# FPGA.net
KiCad netlist of a schematic drawn in Altium Designer
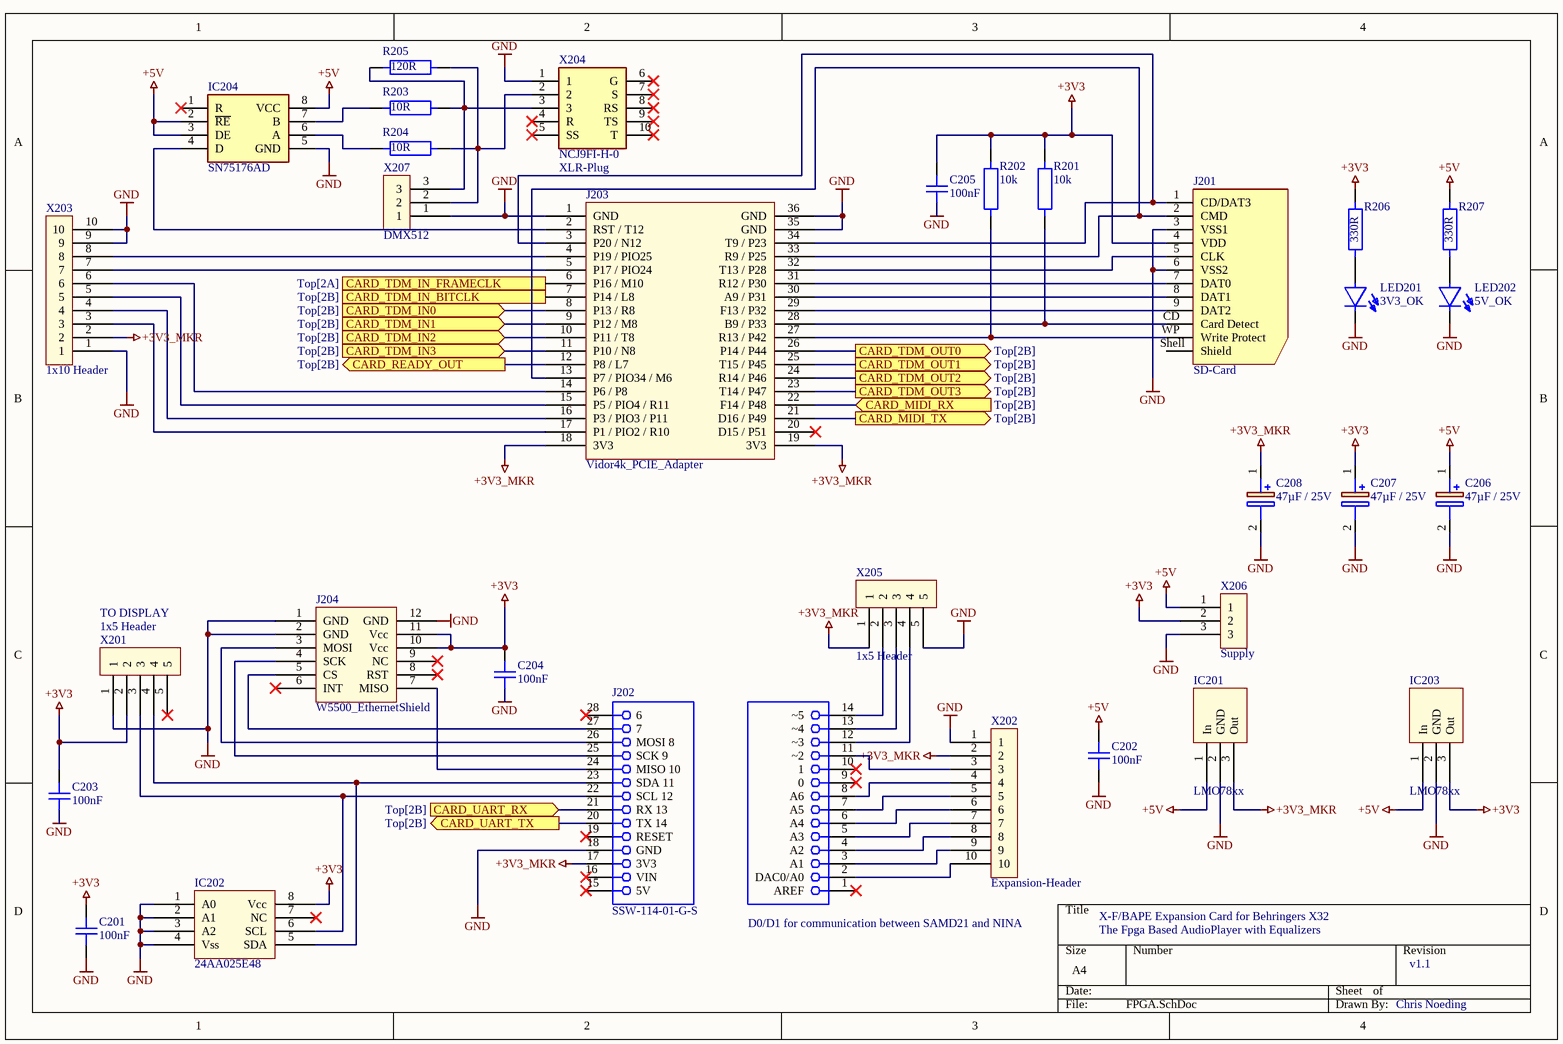
[diagram p0: FPGA.SchDoc]

(export (version "E")
  (design (tool "Eeschema 10.0.6"))
  (components
    (comp (ref "C201")
      (value "100nF")
      (footprint "1206")
      (description "1206_C")
      (libsource (lib "FPGA_Board_Library") (part "1206_C_1nF/63V"))
    )
    (comp (ref "C202")
      (value "100nF")
      (footprint "1206")
      (description "1206_C")
      (libsource (lib "FPGA_Board_Library") (part "1206_C_1nF/63V"))
    )
    (comp (ref "C203")
      (value "100nF")
      (footprint "1206")
      (description "1206_C")
      (libsource (lib "FPGA_Board_Library") (part "1206_C_1nF/63V"))
    )
    (comp (ref "C204")
      (value "100nF")
      (footprint "1206")
      (description "1206_C")
      (libsource (lib "FPGA_Board_Library") (part "1206_C_1nF/63V"))
    )
    (comp (ref "C205")
      (value "100nF")
      (footprint "1206")
      (description "1206_C")
      (libsource (lib "FPGA_Board_Library") (part "1206_C_1nF/63V"))
    )
    (comp (ref "C206")
      (value "47µF / 25V")
      (footprint "SamacSys:CAPPRD200W50D550H1250")
      (description "Capacitor Polarised")
      (fields (field (name "MANUFACTURER_PART_NUMBER") "MAL214256479E3"))
      (libsource (lib "*") (part "MAL214256479E3"))
    )
    (comp (ref "C207")
      (value "47µF / 25V")
      (footprint "SamacSys:CAPPRD200W50D550H1250")
      (description "Capacitor Polarised")
      (fields (field (name "MANUFACTURER_PART_NUMBER") "MAL214256479E3"))
      (libsource (lib "*") (part "MAL214256479E3"))
    )
    (comp (ref "C208")
      (value "47µF / 25V")
      (footprint "SamacSys:CAPPRD200W50D550H1250")
      (description "Capacitor Polarised")
      (fields (field (name "MANUFACTURER_PART_NUMBER") "MAL214256479E3"))
      (libsource (lib "*") (part "MAL214256479E3"))
    )
    (comp (ref "IC201")
      (value "LMO78xx")
      (footprint "LMO78xx")
      (libsource (lib "KDEE_HiResPG") (part "LMO78xx"))
    )
    (comp (ref "IC202")
      (value "24AA025E48")
      (footprint "SOIC-8")
      (libsource (lib "KDEE_HiResPG") (part "24AA025E48"))
    )
    (comp (ref "IC203")
      (value "LMO78xx")
      (footprint "LMO78xx")
      (libsource (lib "KDEE_HiResPG") (part "LMO78xx"))
    )
    (comp (ref "IC204")
      (value "SN75176AD")
      (footprint "SamacSys:SOIC127P600X175-8N")
      (description "Integrated Circuit")
      (fields (field (name "MOUSER PART NUMBER") "595-SN75176AD"))
      (libsource (lib "*") (part "SN75176AD"))
    )
    (comp (ref "J201")
      (value "693061010911")
      (footprint "693061010911")
      (description "WR-CRD SD Card Connector Push & Push with Card Detection")
      (fields (field (name "MANUFACTURER") "Wurth Elektronik"))
      (libsource (lib "SamacSys") (part "693061010911"))
    )
    (comp (ref "J202")
      (value "SSW-114-01-G-S")
      (footprint "SMTC-SSW-114-01-X-S")
      (description "SQ Post Socket, Through-hole, Vertical, -55 to 125 degC, 2.54 mm Pitch, 14-Pin, Female, RoHS")
      (fields (field (name "MANUFACTURER") "Samtec"))
      (libsource (lib "SamacSys") (part "Arduino MKR Vidor 4000"))
    )
    (comp (ref "J203")
      (value "Vidor4k_PCIE_Adapter")
      (footprint "Vidor4K_PCIE_Adapter")
      (libsource (lib "SamacSys") (part "Vidor4k_PCIE_Adapter"))
    )
    (comp (ref "J204")
      (value "W5500_EthernetShield")
      (footprint "W5500_EthernetShield")
      (libsource (lib "KDEE_HiResPG") (part "W5500_EthernetShield"))
    )
    (comp (ref "LED201")
      (value "3V3_OK")
      (footprint "LED 3MM")
      (description "LED 3MM")
      (libsource (lib "FPGA_Board_Library") (part "LED 3MM"))
    )
    (comp (ref "LED202")
      (value "5V_OK")
      (footprint "LED 3MM")
      (description "LED 3MM")
      (libsource (lib "FPGA_Board_Library") (part "LED 3MM"))
    )
    (comp (ref "R201")
      (value "10k")
      (footprint "1206")
      (description "1206_R")
      (libsource (lib "FPGA_Board_Library") (part "1206_R"))
    )
    (comp (ref "R202")
      (value "10k")
      (footprint "1206")
      (description "1206_R")
      (libsource (lib "FPGA_Board_Library") (part "1206_R"))
    )
    (comp (ref "R203")
      (value "10R")
      (footprint "1206")
      (description "1206_R")
      (libsource (lib "FPGA_Board_Library") (part "1206_R"))
    )
    (comp (ref "R204")
      (value "10R")
      (footprint "1206")
      (description "1206_R")
      (libsource (lib "FPGA_Board_Library") (part "1206_R"))
    )
    (comp (ref "R205")
      (value "120R")
      (footprint "1206")
      (description "1206_R")
      (libsource (lib "FPGA_Board_Library") (part "1206_R"))
    )
    (comp (ref "R206")
      (value "330R")
      (footprint "1206")
      (description "1206_R")
      (libsource (lib "FPGA_Board_Library") (part "1206_R"))
    )
    (comp (ref "R207")
      (value "330R")
      (footprint "1206")
      (description "1206_R")
      (libsource (lib "FPGA_Board_Library") (part "1206_R"))
    )
    (comp (ref "X201")
      (value "1x5 Header")
      (footprint "1x5 Header")
      (libsource (lib "KDEE_HiResPG") (part "1x5 Header"))
    )
    (comp (ref "X202")
      (value "Expansion-Header")
      (footprint "1x10 Header")
      (libsource (lib "KDEE_HiResPG") (part "1x10 Header"))
    )
    (comp (ref "X203")
      (value "1x10 Header")
      (footprint "1x10 Header")
      (libsource (lib "") (part "1x10 Header_1"))
    )
    (comp (ref "X204")
      (value "NCJ9FI-H-0")
      (footprint "SamacSys:NCJ9FIH0")
      (description "Connector")
      (fields (field (name "MOUSER PART NUMBER") "568-NCJ9FI-H-O"))
      (libsource (lib "SamacSys") (part "NCJ9FI-H-0"))
    )
    (comp (ref "X205")
      (value "1x5 Header")
      (footprint "1x5 Header")
      (libsource (lib "KDEE_HiResPG") (part "1x5 Header"))
    )
    (comp (ref "X206")
      (value "Supply")
      (footprint "1x3 Jumper")
      (libsource (lib "KDEE_HiResPG") (part "1x3 Jumper"))
    )
    (comp (ref "X207") (value "DMX512") (footprint "1x3 Jumper") (libsource (lib "") (part "1x3 Jumper_1")))
  )
  (nets
    (net (code "1") (name "+3V3") (class "Default")
      (node (ref "C201") (pin "1") (pinfunction "1_1") (pintype "passive"))
      (node (ref "C203") (pin "1") (pinfunction "1_1") (pintype "passive"))
      (node (ref "C204") (pin "1") (pinfunction "1_1") (pintype "passive"))
      (node (ref "C205") (pin "1") (pinfunction "1_1") (pintype "passive"))
      (node (ref "C207") (pin "1") (pinfunction "+_1") (pintype "passive"))
      (node (ref "IC202") (pin "8") (pinfunction "Vcc_8") (pintype "passive"))
      (node (ref "IC203") (pin "3") (pinfunction "Out_3") (pintype "passive"))
      (node (ref "J201") (pin "4") (pinfunction "VDD_4") (pintype "passive"))
      (node (ref "J204") (pin "10") (pinfunction "Vcc_10") (pintype "passive"))
      (node (ref "J204") (pin "11") (pinfunction "Vcc_11") (pintype "passive"))
      (node (ref "R201") (pin "2") (pinfunction "2_2") (pintype "passive"))
      (node (ref "R202") (pin "2") (pinfunction "2_2") (pintype "passive"))
      (node (ref "R206") (pin "1") (pinfunction "1_1") (pintype "passive"))
      (node (ref "X201") (pin "2") (pinfunction "2_2") (pintype "passive"))
      (node (ref "X206") (pin "2") (pinfunction "2_2") (pintype "passive"))
    )
    (net (code "2") (name "+3V3_MKR") (class "Default")
      (node (ref "C208") (pin "1") (pinfunction "+_1") (pintype "passive"))
      (node (ref "IC201") (pin "3") (pinfunction "Out_3") (pintype "passive"))
      (node (ref "J202") (pin "17") (pinfunction "3V3_17") (pintype "passive"))
      (node (ref "J203") (pin "18") (pinfunction "3V3_18") (pintype "passive"))
      (node (ref "J203") (pin "19") (pinfunction "3V3_19") (pintype "passive"))
      (node (ref "X202") (pin "2") (pinfunction "2_2") (pintype "passive"))
      (node (ref "X203") (pin "2") (pinfunction "2_2") (pintype "passive"))
      (node (ref "X205") (pin "1") (pinfunction "1_1") (pintype "passive"))
    )
    (net (code "3") (name "+5V") (class "Default")
      (node (ref "C202") (pin "1") (pinfunction "1_1") (pintype "passive"))
      (node (ref "C206") (pin "1") (pinfunction "+_1") (pintype "passive"))
      (node (ref "IC201") (pin "1") (pinfunction "In_1") (pintype "passive"))
      (node (ref "IC203") (pin "1") (pinfunction "In_1") (pintype "passive"))
      (node (ref "IC204") (pin "2") (pinfunction "~{RE}_2") (pintype "passive"))
      (node (ref "IC204") (pin "3") (pinfunction "DE_3") (pintype "passive"))
      (node (ref "IC204") (pin "8") (pinfunction "VCC_8") (pintype "passive"))
      (node (ref "R207") (pin "1") (pinfunction "1_1") (pintype "passive"))
      (node (ref "X206") (pin "1") (pinfunction "1_1") (pintype "passive"))
    )
    (net (code "4") (name "/CARD_MIDI_RX") (class "Default")
      (node (ref "J203") (pin "22") (pinfunction "F14_/_P48_22") (pintype "passive"))
    )
    (net (code "5") (name "/CARD_MIDI_TX") (class "Default")
      (node (ref "J203") (pin "21") (pinfunction "D16_/_P49_21") (pintype "passive"))
    )
    (net (code "6") (name "/CARD_READY_OUT") (class "Default")
      (node (ref "J203") (pin "12") (pinfunction "P8_/_L7_12") (pintype "passive"))
    )
    (net (code "7") (name "/CARD_TDM_IN0") (class "Default")
      (node (ref "J203") (pin "8") (pinfunction "P13_/_R8_8") (pintype "passive"))
    )
    (net (code "8") (name "/CARD_TDM_IN1") (class "Default")
      (node (ref "J203") (pin "9") (pinfunction "P12_/_M8_9") (pintype "passive"))
    )
    (net (code "9") (name "/CARD_TDM_IN2") (class "Default")
      (node (ref "J203") (pin "10") (pinfunction "P11_/_T8_10") (pintype "passive"))
    )
    (net (code "10") (name "/CARD_TDM_IN3") (class "Default")
      (node (ref "J203") (pin "11") (pinfunction "P10_/_N8_11") (pintype "passive"))
    )
    (net (code "11") (name "/CARD_TDM_IN_BITCLK") (class "Default")
      (node (ref "J203") (pin "7") (pinfunction "P14_/_L8_7") (pintype "passive"))
    )
    (net (code "12") (name "/CARD_TDM_IN_FRAMECLK") (class "Default")
      (node (ref "J203") (pin "6") (pinfunction "P16_/_M10_6") (pintype "passive"))
    )
    (net (code "13") (name "/CARD_TDM_OUT0") (class "Default")
      (node (ref "J203") (pin "26") (pinfunction "P14_/_P44_26") (pintype "passive"))
    )
    (net (code "14") (name "/CARD_TDM_OUT1") (class "Default")
      (node (ref "J203") (pin "25") (pinfunction "T15_/_P45_25") (pintype "passive"))
    )
    (net (code "15") (name "/CARD_TDM_OUT2") (class "Default")
      (node (ref "J203") (pin "24") (pinfunction "R14_/_P46_24") (pintype "passive"))
    )
    (net (code "16") (name "/CARD_TDM_OUT3") (class "Default")
      (node (ref "J203") (pin "23") (pinfunction "T14_/_P47_23") (pintype "passive"))
    )
    (net (code "17") (name "/CARD_UART_RX") (class "Default")
      (node (ref "J202") (pin "21") (pinfunction "RX_13_21") (pintype "passive"))
    )
    (net (code "18") (name "/CARD_UART_TX") (class "Default")
      (node (ref "J202") (pin "20") (pinfunction "TX_14_20") (pintype "passive"))
    )
    (net (code "19") (name "GND") (class "Default")
      (node (ref "C201") (pin "2") (pinfunction "2_2") (pintype "passive"))
      (node (ref "C202") (pin "2") (pinfunction "2_2") (pintype "passive"))
      (node (ref "C203") (pin "2") (pinfunction "2_2") (pintype "passive"))
      (node (ref "C204") (pin "2") (pinfunction "2_2") (pintype "passive"))
      (node (ref "C205") (pin "2") (pinfunction "2_2") (pintype "passive"))
      (node (ref "C206") (pin "2") (pinfunction "-_2") (pintype "passive"))
      (node (ref "C207") (pin "2") (pinfunction "-_2") (pintype "passive"))
      (node (ref "C208") (pin "2") (pinfunction "-_2") (pintype "passive"))
      (node (ref "IC201") (pin "2") (pinfunction "GND_2") (pintype "passive"))
      (node (ref "IC202") (pin "1") (pinfunction "A0_1") (pintype "passive"))
      (node (ref "IC202") (pin "2") (pinfunction "A1_2") (pintype "passive"))
      (node (ref "IC202") (pin "3") (pinfunction "A2_3") (pintype "passive"))
      (node (ref "IC202") (pin "4") (pinfunction "Vss_4") (pintype "passive"))
      (node (ref "IC203") (pin "2") (pinfunction "GND_2") (pintype "passive"))
      (node (ref "IC204") (pin "5") (pinfunction "GND_5") (pintype "passive"))
      (node (ref "J201") (pin "3") (pinfunction "VSS1_3") (pintype "passive"))
      (node (ref "J201") (pin "6") (pinfunction "VSS2_6") (pintype "passive"))
      (node (ref "J202") (pin "18") (pinfunction "GND_18") (pintype "passive"))
      (node (ref "J203") (pin "1") (pinfunction "GND_1") (pintype "passive"))
      (node (ref "J203") (pin "35") (pinfunction "GND_35") (pintype "passive"))
      (node (ref "J203") (pin "36") (pinfunction "GND_36") (pintype "passive"))
      (node (ref "J204") (pin "1") (pinfunction "GND_1") (pintype "passive"))
      (node (ref "J204") (pin "12") (pinfunction "GND_12") (pintype "passive"))
      (node (ref "J204") (pin "2") (pinfunction "GND_2") (pintype "passive"))
      (node (ref "LED201") (pin "2") (pintype "passive"))
      (node (ref "LED202") (pin "2") (pintype "passive"))
      (node (ref "X201") (pin "1") (pinfunction "1_1") (pintype "passive"))
      (node (ref "X202") (pin "1") (pinfunction "1_1") (pintype "passive"))
      (node (ref "X203") (pin "1") (pinfunction "1_1") (pintype "passive"))
      (node (ref "X203") (pin "10") (pinfunction "10_10") (pintype "passive"))
      (node (ref "X203") (pin "9") (pinfunction "9_9") (pintype "passive"))
      (node (ref "X204") (pin "1") (pinfunction "1_1") (pintype "passive"))
      (node (ref "X205") (pin "5") (pinfunction "5_5") (pintype "passive"))
      (node (ref "X206") (pin "3") (pinfunction "3_3") (pintype "passive"))
      (node (ref "X207") (pin "1") (pinfunction "1_1") (pintype "passive"))
    )
    (net (code "20") (name "Net-(IC202-SCL)") (class "Default")
      (node (ref "IC202") (pin "6") (pinfunction "SCL_6") (pintype "passive"))
      (node (ref "J202") (pin "22") (pinfunction "SCL_12_22") (pintype "passive"))
      (node (ref "X201") (pin "3") (pinfunction "3_3") (pintype "passive"))
    )
    (net (code "21") (name "Net-(IC202-SDA)") (class "Default")
      (node (ref "IC202") (pin "5") (pinfunction "SDA_5") (pintype "passive"))
      (node (ref "J202") (pin "23") (pinfunction "SDA_11_23") (pintype "passive"))
      (node (ref "X201") (pin "4") (pinfunction "4_4") (pintype "passive"))
    )
    (net (code "22") (name "Net-(IC204-A)") (class "Default")
      (node (ref "IC204") (pin "6") (pinfunction "A_6") (pintype "passive"))
      (node (ref "R204") (pin "1") (pinfunction "1_1") (pintype "passive"))
    )
    (net (code "23") (name "Net-(IC204-B)") (class "Default")
      (node (ref "IC204") (pin "7") (pinfunction "B_7") (pintype "passive"))
      (node (ref "R203") (pin "1") (pinfunction "1_1") (pintype "passive"))
    )
    (net (code "24") (name "Net-(IC204-D)") (class "Default")
      (node (ref "IC204") (pin "4") (pinfunction "D_4") (pintype "passive"))
      (node (ref "J203") (pin "2") (pinfunction "RST_/_T12_2") (pintype "passive"))
    )
    (net (code "25") (name "Net-(J201-CD{slash}DAT3)") (class "Default")
      (node (ref "J201") (pin "1") (pinfunction "CD/DAT3_1") (pintype "passive"))
      (node (ref "J203") (pin "3") (pinfunction "P20_/_N12_3") (pintype "passive"))
      (node (ref "J203") (pin "34") (pinfunction "T9_/_P23_34") (pintype "passive"))
    )
    (net (code "26") (name "Net-(J201-CLK)") (class "Default")
      (node (ref "J201") (pin "5") (pinfunction "CLK_5") (pintype "passive"))
      (node (ref "J203") (pin "32") (pinfunction "T13_/_P28_32") (pintype "passive"))
    )
    (net (code "27") (name "Net-(J201-CMD)") (class "Default")
      (node (ref "J201") (pin "2") (pinfunction "CMD_2") (pintype "passive"))
      (node (ref "J203") (pin "13") (pinfunction "P7_/_PIO34_/_M6_13") (pintype "passive"))
      (node (ref "J203") (pin "33") (pinfunction "R9_/_P25_33") (pintype "passive"))
    )
    (net (code "28") (name "Net-(J201-Card_Detect)") (class "Default")
      (node (ref "J201") (pin "CD") (pinfunction "Card_Detect_CD") (pintype "passive"))
      (node (ref "J203") (pin "28") (pinfunction "B9_/_P33_28") (pintype "passive"))
      (node (ref "R201") (pin "1") (pinfunction "1_1") (pintype "passive"))
    )
    (net (code "29") (name "Net-(J201-DAT0)") (class "Default")
      (node (ref "J201") (pin "7") (pinfunction "DAT0_7") (pintype "passive"))
      (node (ref "J203") (pin "31") (pinfunction "R12_/_P30_31") (pintype "passive"))
    )
    (net (code "30") (name "Net-(J201-DAT1)") (class "Default")
      (node (ref "J201") (pin "8") (pinfunction "DAT1_8") (pintype "passive"))
      (node (ref "J203") (pin "30") (pinfunction "A9_/_P31_30") (pintype "passive"))
    )
    (net (code "31") (name "Net-(J201-DAT2)") (class "Default")
      (node (ref "J201") (pin "9") (pinfunction "DAT2_9") (pintype "passive"))
      (node (ref "J203") (pin "29") (pinfunction "F13_/_P32_29") (pintype "passive"))
    )
    (net (code "32") (name "Net-(J201-Write_Protect)") (class "Default")
      (node (ref "J201") (pin "WP") (pinfunction "Write_Protect_WP") (pintype "passive"))
      (node (ref "J203") (pin "27") (pinfunction "R13_/_P42_27") (pintype "passive"))
      (node (ref "R202") (pin "1") (pinfunction "1_1") (pintype "passive"))
    )
    (net (code "33") (name "Net-(J202-7)") (class "Default")
      (node (ref "J202") (pin "27") (pinfunction "7_27") (pintype "passive"))
      (node (ref "J204") (pin "5") (pinfunction "CS_5") (pintype "passive"))
    )
    (net (code "34") (name "Net-(J202-A1)") (class "Default")
      (node (ref "J202") (pin "3") (pinfunction "A1_3") (pintype "passive"))
      (node (ref "X202") (pin "9") (pinfunction "9_9") (pintype "passive"))
    )
    (net (code "35") (name "Net-(J202-A2)") (class "Default")
      (node (ref "J202") (pin "4") (pinfunction "A2_4") (pintype "passive"))
      (node (ref "X202") (pin "8") (pinfunction "8_8") (pintype "passive"))
    )
    (net (code "36") (name "Net-(J202-A3)") (class "Default")
      (node (ref "J202") (pin "5") (pinfunction "A3_5") (pintype "passive"))
      (node (ref "X202") (pin "7") (pinfunction "7_7") (pintype "passive"))
    )
    (net (code "37") (name "Net-(J202-A4)") (class "Default")
      (node (ref "J202") (pin "6") (pinfunction "A4_6") (pintype "passive"))
      (node (ref "X202") (pin "6") (pinfunction "6_6") (pintype "passive"))
    )
    (net (code "38") (name "Net-(J202-A5)") (class "Default")
      (node (ref "J202") (pin "7") (pinfunction "A5_7") (pintype "passive"))
      (node (ref "X202") (pin "5") (pinfunction "5_5") (pintype "passive"))
    )
    (net (code "39") (name "Net-(J202-A6)") (class "Default")
      (node (ref "J202") (pin "8") (pinfunction "A6_8") (pintype "passive"))
      (node (ref "X202") (pin "4") (pinfunction "4_4") (pintype "passive"))
    )
    (net (code "40") (name "Net-(J202-DAC0{slash}A0)") (class "Default")
      (node (ref "J202") (pin "2") (pinfunction "DAC0/A0_2") (pintype "passive"))
      (node (ref "X202") (pin "10") (pinfunction "10_10") (pintype "passive"))
    )
    (net (code "41") (name "Net-(J202-MISO_10)") (class "Default")
      (node (ref "J202") (pin "24") (pinfunction "MISO_10_24") (pintype "passive"))
      (node (ref "J204") (pin "7") (pinfunction "MISO_7") (pintype "passive"))
    )
    (net (code "42") (name "Net-(J202-MOSI_8)") (class "Default")
      (node (ref "J202") (pin "26") (pinfunction "MOSI_8_26") (pintype "passive"))
      (node (ref "J204") (pin "3") (pinfunction "MOSI_3") (pintype "passive"))
    )
    (net (code "43") (name "Net-(J202-SCK_9)") (class "Default")
      (node (ref "J202") (pin "25") (pinfunction "SCK_9_25") (pintype "passive"))
      (node (ref "J204") (pin "4") (pinfunction "SCK_4") (pintype "passive"))
    )
    (net (code "44") (name "Net-(J202-~2)") (class "Default")
      (node (ref "J202") (pin "11") (pinfunction "~2_11") (pintype "passive"))
      (node (ref "X202") (pin "3") (pinfunction "3_3") (pintype "passive"))
    )
    (net (code "45") (name "Net-(J202-~3)") (class "Default")
      (node (ref "J202") (pin "12") (pinfunction "~3_12") (pintype "passive"))
      (node (ref "X205") (pin "4") (pinfunction "4_4") (pintype "passive"))
    )
    (net (code "46") (name "Net-(J202-~4)") (class "Default")
      (node (ref "J202") (pin "13") (pinfunction "~4_13") (pintype "passive"))
      (node (ref "X205") (pin "3") (pinfunction "3_3") (pintype "passive"))
    )
    (net (code "47") (name "Net-(J202-~5)") (class "Default")
      (node (ref "J202") (pin "14") (pinfunction "~5_14") (pintype "passive"))
      (node (ref "X205") (pin "2") (pinfunction "2_2") (pintype "passive"))
    )
    (net (code "48") (name "Net-(J203-P1_{slash}_PIO2_{slash}_R10)") (class "Default")
      (node (ref "J203") (pin "17") (pinfunction "P1_/_PIO2_/_R10_17") (pintype "passive"))
      (node (ref "X203") (pin "3") (pinfunction "3_3") (pintype "passive"))
    )
    (net (code "49") (name "Net-(J203-P3_{slash}_PIO3_{slash}_P11)") (class "Default")
      (node (ref "J203") (pin "16") (pinfunction "P3_/_PIO3_/_P11_16") (pintype "passive"))
      (node (ref "X203") (pin "4") (pinfunction "4_4") (pintype "passive"))
    )
    (net (code "50") (name "Net-(J203-P5_{slash}_PIO4_{slash}_R11)") (class "Default")
      (node (ref "J203") (pin "15") (pinfunction "P5_/_PIO4_/_R11_15") (pintype "passive"))
      (node (ref "X203") (pin "5") (pinfunction "5_5") (pintype "passive"))
    )
    (net (code "51") (name "Net-(J203-P6_{slash}_P8)") (class "Default")
      (node (ref "J203") (pin "14") (pinfunction "P6_/_P8_14") (pintype "passive"))
      (node (ref "X203") (pin "6") (pinfunction "6_6") (pintype "passive"))
    )
    (net (code "52") (name "Net-(J203-P17_{slash}_PIO24)") (class "Default")
      (node (ref "J203") (pin "5") (pinfunction "P17_/_PIO24_5") (pintype "passive"))
      (node (ref "X203") (pin "7") (pinfunction "7_7") (pintype "passive"))
    )
    (net (code "53") (name "Net-(J203-P19_{slash}_PIO25)") (class "Default")
      (node (ref "J203") (pin "4") (pinfunction "P19_/_PIO25_4") (pintype "passive"))
      (node (ref "X203") (pin "8") (pinfunction "8_8") (pintype "passive"))
    )
    (net (code "54") (name "Net-(LED201-Pad1)") (class "Default")
      (node (ref "LED201") (pin "1") (pintype "passive"))
      (node (ref "R206") (pin "2") (pinfunction "2_2") (pintype "passive"))
    )
    (net (code "55") (name "Net-(LED202-Pad1)") (class "Default")
      (node (ref "LED202") (pin "1") (pintype "passive"))
      (node (ref "R207") (pin "2") (pinfunction "2_2") (pintype "passive"))
    )
    (net (code "56") (name "Net-(R203-Pad2)") (class "Default")
      (node (ref "R203") (pin "2") (pinfunction "2_2") (pintype "passive"))
      (node (ref "R205") (pin "1") (pinfunction "1_1") (pintype "passive"))
      (node (ref "X204") (pin "3") (pinfunction "3_3") (pintype "passive"))
      (node (ref "X207") (pin "3") (pinfunction "3_3") (pintype "passive"))
    )
    (net (code "57") (name "Net-(R204-Pad2)") (class "Default")
      (node (ref "R204") (pin "2") (pinfunction "2_2") (pintype "passive"))
      (node (ref "R205") (pin "2") (pinfunction "2_2") (pintype "passive"))
      (node (ref "X204") (pin "2") (pinfunction "2_2") (pintype "passive"))
      (node (ref "X207") (pin "2") (pinfunction "2_2") (pintype "passive"))
    )
    (net (code "58") (name "unconnected-(IC202-NC-Pad7)") (class "Default")
      (node (ref "IC202") (pin "7") (pinfunction "NC_7") (pintype "passive+no_connect"))
    )
    (net (code "59") (name "unconnected-(IC204-R-Pad1)") (class "Default")
      (node (ref "IC204") (pin "1") (pinfunction "R_1") (pintype "passive+no_connect"))
    )
    (net (code "60") (name "unconnected-(J201-Shield-PadShell)") (class "Default")
      (node (ref "J201") (pin "Shell") (pinfunction "Shield_Shell") (pintype "passive"))
    )
    (net (code "61") (name "unconnected-(J202-0-Pad9)") (class "Default")
      (node (ref "J202") (pin "9") (pinfunction "0_9") (pintype "passive+no_connect"))
    )
    (net (code "62") (name "unconnected-(J202-1-Pad10)") (class "Default")
      (node (ref "J202") (pin "10") (pinfunction "1_10") (pintype "passive+no_connect"))
    )
    (net (code "63") (name "unconnected-(J202-5V-Pad15)") (class "Default")
      (node (ref "J202") (pin "15") (pinfunction "5V_15") (pintype "passive+no_connect"))
    )
    (net (code "64") (name "unconnected-(J202-6-Pad28)") (class "Default")
      (node (ref "J202") (pin "28") (pinfunction "6_28") (pintype "passive+no_connect"))
    )
    (net (code "65") (name "unconnected-(J202-AREF-Pad1)") (class "Default")
      (node (ref "J202") (pin "1") (pinfunction "AREF_1") (pintype "passive+no_connect"))
    )
    (net (code "66") (name "unconnected-(J202-RESET-Pad19)") (class "Default")
      (node (ref "J202") (pin "19") (pinfunction "RESET_19") (pintype "passive+no_connect"))
    )
    (net (code "67") (name "unconnected-(J202-VIN-Pad16)") (class "Default")
      (node (ref "J202") (pin "16") (pinfunction "VIN_16") (pintype "passive+no_connect"))
    )
    (net (code "68") (name "unconnected-(J203-D15_{slash}_P51-Pad20)") (class "Default")
      (node (ref "J203") (pin "20") (pinfunction "D15_/_P51_20") (pintype "passive+no_connect"))
    )
    (net (code "69") (name "unconnected-(J204-INT-Pad6)") (class "Default")
      (node (ref "J204") (pin "6") (pinfunction "INT_6") (pintype "passive+no_connect"))
    )
    (net (code "70") (name "unconnected-(J204-NC-Pad9)") (class "Default")
      (node (ref "J204") (pin "9") (pinfunction "NC_9") (pintype "passive+no_connect"))
    )
    (net (code "71") (name "unconnected-(J204-RST-Pad8)") (class "Default")
      (node (ref "J204") (pin "8") (pinfunction "RST_8") (pintype "passive+no_connect"))
    )
    (net (code "72") (name "unconnected-(X201-Pad5)") (class "Default")
      (node (ref "X201") (pin "5") (pinfunction "5_5") (pintype "passive+no_connect"))
    )
    (net (code "73") (name "unconnected-(X204-G-Pad6)") (class "Default")
      (node (ref "X204") (pin "6") (pinfunction "G_6") (pintype "passive+no_connect"))
    )
    (net (code "74") (name "unconnected-(X204-R-Pad4)") (class "Default")
      (node (ref "X204") (pin "4") (pinfunction "R_4") (pintype "passive+no_connect"))
    )
    (net (code "75") (name "unconnected-(X204-RS-Pad8)") (class "Default")
      (node (ref "X204") (pin "8") (pinfunction "RS_8") (pintype "passive+no_connect"))
    )
    (net (code "76") (name "unconnected-(X204-S-Pad7)") (class "Default")
      (node (ref "X204") (pin "7") (pinfunction "S_7") (pintype "passive+no_connect"))
    )
    (net (code "77") (name "unconnected-(X204-SS-Pad5)") (class "Default")
      (node (ref "X204") (pin "5") (pinfunction "SS_5") (pintype "passive+no_connect"))
    )
    (net (code "78") (name "unconnected-(X204-T-Pad10)") (class "Default")
      (node (ref "X204") (pin "10") (pinfunction "T_10") (pintype "passive+no_connect"))
    )
    (net (code "79") (name "unconnected-(X204-TS-Pad9)") (class "Default")
      (node (ref "X204") (pin "9") (pinfunction "TS_9") (pintype "passive+no_connect"))
    )
  )
)
